# signal1.net
KiCad netlist of a schematic drawn in Altium Designer
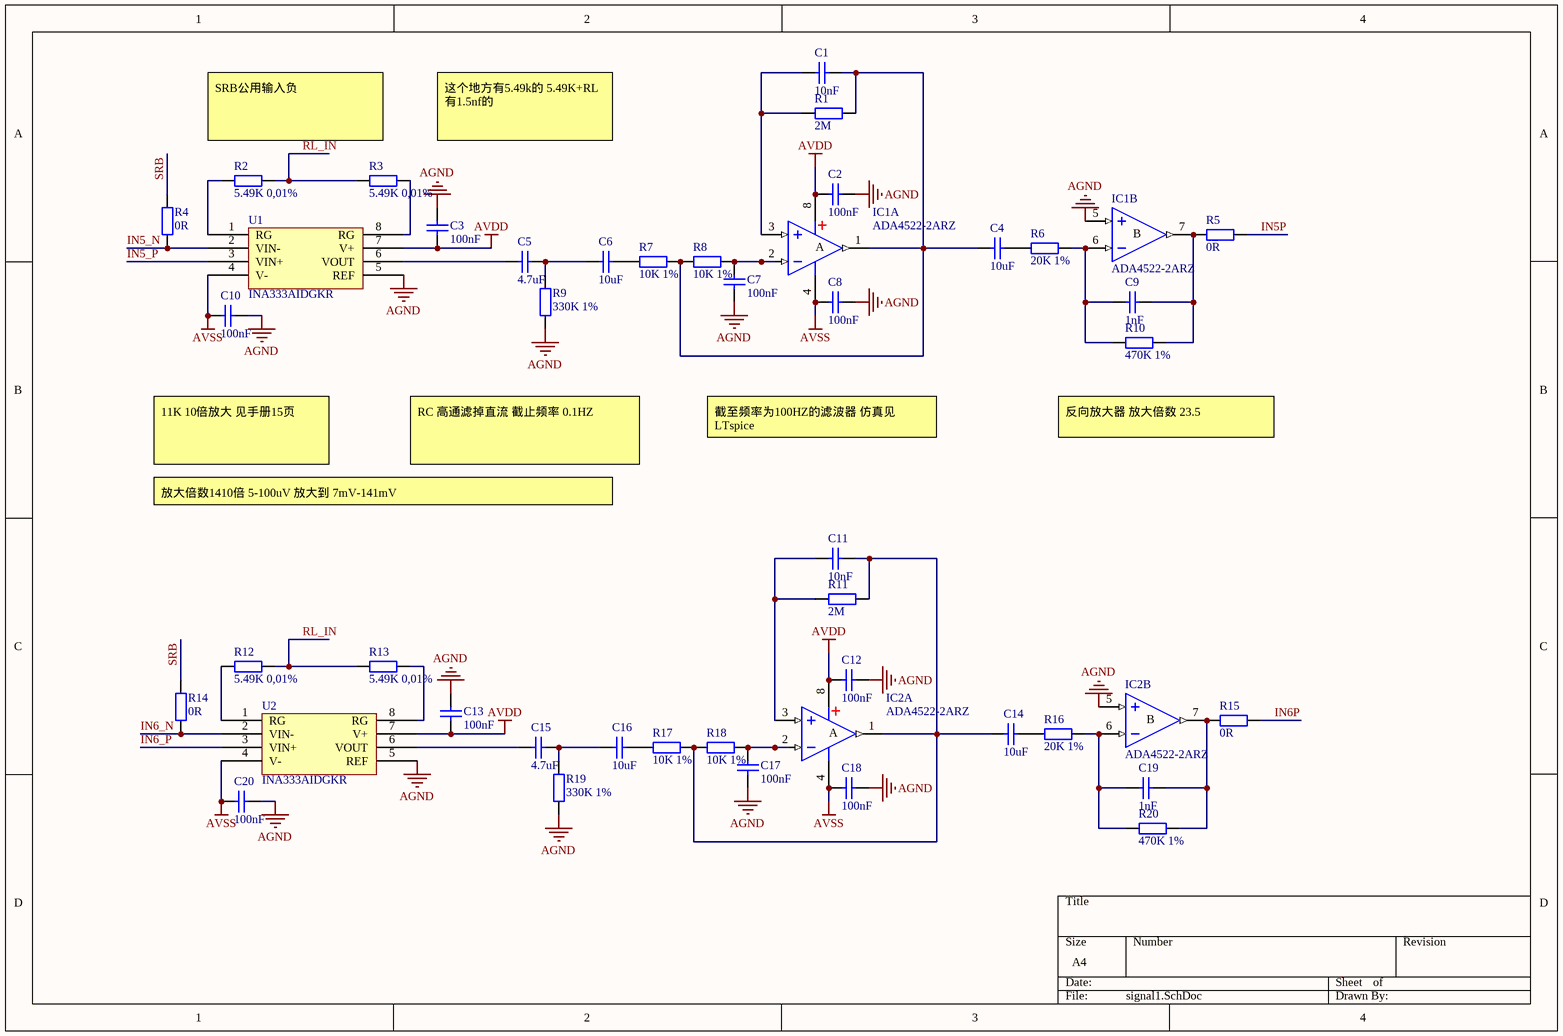
[diagram p0: signal1.SchDoc]

(export (version "E")
  (design (tool "Eeschema 10.0.6"))
  (components
    (comp (ref "C1")
      (value "10nF")
      (footprint "C0603_L")
      (description "贴片电容/MLCC电容")
      (libsource (lib "0.1 - 电阻-电容-电感-保险丝-晶振-晶体-磁珠-电位器-法拉电容-馈通电容") (part "C"))
    )
    (comp (ref "C2")
      (value "100nF")
      (footprint "C0603_L")
      (description "贴片电容/MLCC电容")
      (libsource (lib "0.1 - 电阻-电容-电感-保险丝-晶振-晶体-磁珠-电位器-法拉电容-馈通电容") (part "C"))
    )
    (comp (ref "C3")
      (value "100nF")
      (footprint "C0603_L")
      (description "贴片电容/MLCC电容")
      (libsource (lib "0.1 - 电阻-电容-电感-保险丝-晶振-晶体-磁珠-电位器-法拉电容-馈通电容") (part "C"))
    )
    (comp (ref "C4")
      (value "10uF")
      (footprint "C0603_L")
      (description "贴片电容/MLCC电容")
      (libsource (lib "0.1 - 电阻-电容-电感-保险丝-晶振-晶体-磁珠-电位器-法拉电容-馈通电容") (part "C"))
    )
    (comp (ref "C5")
      (value "4.7uF")
      (footprint "C0603_L")
      (description "贴片电容/MLCC电容")
      (libsource (lib "0.1 - 电阻-电容-电感-保险丝-晶振-晶体-磁珠-电位器-法拉电容-馈通电容") (part "C"))
    )
    (comp (ref "C6")
      (value "10uF")
      (footprint "C0603_L")
      (description "贴片电容/MLCC电容")
      (libsource (lib "0.1 - 电阻-电容-电感-保险丝-晶振-晶体-磁珠-电位器-法拉电容-馈通电容") (part "C"))
    )
    (comp (ref "C7")
      (value "100nF")
      (footprint "C0603_L")
      (description "贴片电容/MLCC电容")
      (libsource (lib "0.1 - 电阻-电容-电感-保险丝-晶振-晶体-磁珠-电位器-法拉电容-馈通电容") (part "C"))
    )
    (comp (ref "C8")
      (value "100nF")
      (footprint "C0603_L")
      (description "贴片电容/MLCC电容")
      (libsource (lib "0.1 - 电阻-电容-电感-保险丝-晶振-晶体-磁珠-电位器-法拉电容-馈通电容") (part "C"))
    )
    (comp (ref "C9")
      (value "1nF")
      (footprint "C0603_L")
      (description "贴片电容/MLCC电容")
      (libsource (lib "0.1 - 电阻-电容-电感-保险丝-晶振-晶体-磁珠-电位器-法拉电容-馈通电容") (part "C"))
    )
    (comp (ref "C10")
      (value "100nF")
      (footprint "C0603_L")
      (description "贴片电容/MLCC电容")
      (libsource (lib "0.1 - 电阻-电容-电感-保险丝-晶振-晶体-磁珠-电位器-法拉电容-馈通电容") (part "C"))
    )
    (comp (ref "C11")
      (value "10nF")
      (footprint "C0603_L")
      (description "贴片电容/MLCC电容")
      (libsource (lib "0.1 - 电阻-电容-电感-保险丝-晶振-晶体-磁珠-电位器-法拉电容-馈通电容") (part "C"))
    )
    (comp (ref "C12")
      (value "100nF")
      (footprint "C0603_L")
      (description "贴片电容/MLCC电容")
      (libsource (lib "0.1 - 电阻-电容-电感-保险丝-晶振-晶体-磁珠-电位器-法拉电容-馈通电容") (part "C"))
    )
    (comp (ref "C13")
      (value "100nF")
      (footprint "C0603_L")
      (description "贴片电容/MLCC电容")
      (libsource (lib "0.1 - 电阻-电容-电感-保险丝-晶振-晶体-磁珠-电位器-法拉电容-馈通电容") (part "C"))
    )
    (comp (ref "C14")
      (value "10uF")
      (footprint "C0603_L")
      (description "贴片电容/MLCC电容")
      (libsource (lib "0.1 - 电阻-电容-电感-保险丝-晶振-晶体-磁珠-电位器-法拉电容-馈通电容") (part "C"))
    )
    (comp (ref "C15")
      (value "4.7uF")
      (footprint "C0603_L")
      (description "贴片电容/MLCC电容")
      (libsource (lib "0.1 - 电阻-电容-电感-保险丝-晶振-晶体-磁珠-电位器-法拉电容-馈通电容") (part "C"))
    )
    (comp (ref "C16")
      (value "10uF")
      (footprint "C0603_L")
      (description "贴片电容/MLCC电容")
      (libsource (lib "0.1 - 电阻-电容-电感-保险丝-晶振-晶体-磁珠-电位器-法拉电容-馈通电容") (part "C"))
    )
    (comp (ref "C17")
      (value "100nF")
      (footprint "C0603_L")
      (description "贴片电容/MLCC电容")
      (libsource (lib "0.1 - 电阻-电容-电感-保险丝-晶振-晶体-磁珠-电位器-法拉电容-馈通电容") (part "C"))
    )
    (comp (ref "C18")
      (value "100nF")
      (footprint "C0603_L")
      (description "贴片电容/MLCC电容")
      (libsource (lib "0.1 - 电阻-电容-电感-保险丝-晶振-晶体-磁珠-电位器-法拉电容-馈通电容") (part "C"))
    )
    (comp (ref "C19")
      (value "1nF")
      (footprint "C0603_L")
      (description "贴片电容/MLCC电容")
      (libsource (lib "0.1 - 电阻-电容-电感-保险丝-晶振-晶体-磁珠-电位器-法拉电容-馈通电容") (part "C"))
    )
    (comp (ref "C20")
      (value "100nF")
      (footprint "C0603_L")
      (description "贴片电容/MLCC电容")
      (libsource (lib "0.1 - 电阻-电容-电感-保险丝-晶振-晶体-磁珠-电位器-法拉电容-馈通电容") (part "C"))
    )
    (comp (ref "IC1")
      (value "ADA4522-2ARZ")
      (footprint "SOIC-8")
      (description "双通道55V、EMI增强型、零漂移、超低噪声、RRO运算放大器")
      (libsource (lib "HT") (part "ADA4522-2ARZ"))
    )
    (comp (ref "IC2")
      (value "ADA4522-2ARZ")
      (footprint "SOIC-8")
      (description "双通道55V、EMI增强型、零漂移、超低噪声、RRO运算放大器")
      (libsource (lib "HT") (part "ADA4522-2ARZ"))
    )
    (comp (ref "R1")
      (value "2M")
      (footprint "R0603_L")
      (description "贴片电阻")
      (libsource (lib "0.1 - 电阻-电容-电感-保险丝-晶振-晶体-磁珠-电位器-法拉电容-馈通电容") (part "R"))
    )
    (comp (ref "R2")
      (value "5.49K 0,01%")
      (footprint "R0603_M")
      (description "贴片电阻")
      (libsource (lib "0.1 - 电阻-电容-电感-保险丝-晶振-晶体-磁珠-电位器-法拉电容-馈通电容") (part "R"))
    )
    (comp (ref "R3")
      (value "5.49K 0,01%")
      (footprint "R0603_M")
      (description "贴片电阻")
      (libsource (lib "0.1 - 电阻-电容-电感-保险丝-晶振-晶体-磁珠-电位器-法拉电容-馈通电容") (part "R"))
    )
    (comp (ref "R4")
      (value "0R")
      (footprint "R0603_L")
      (description "贴片电阻")
      (libsource (lib "0.1 - 电阻-电容-电感-保险丝-晶振-晶体-磁珠-电位器-法拉电容-馈通电容") (part "R"))
    )
    (comp (ref "R5")
      (value "0R")
      (footprint "R0603_L")
      (description "贴片电阻")
      (libsource (lib "0.1 - 电阻-电容-电感-保险丝-晶振-晶体-磁珠-电位器-法拉电容-馈通电容") (part "R"))
    )
    (comp (ref "R6")
      (value "20K 1%")
      (footprint "R0603_L")
      (description "贴片电阻")
      (libsource (lib "0.1 - 电阻-电容-电感-保险丝-晶振-晶体-磁珠-电位器-法拉电容-馈通电容") (part "R"))
    )
    (comp (ref "R7")
      (value "10K 1%")
      (footprint "R0603_L")
      (description "贴片电阻")
      (libsource (lib "0.1 - 电阻-电容-电感-保险丝-晶振-晶体-磁珠-电位器-法拉电容-馈通电容") (part "R"))
    )
    (comp (ref "R8")
      (value "10K 1%")
      (footprint "R0603_L")
      (description "贴片电阻")
      (libsource (lib "0.1 - 电阻-电容-电感-保险丝-晶振-晶体-磁珠-电位器-法拉电容-馈通电容") (part "R"))
    )
    (comp (ref "R9")
      (value "330K 1%")
      (footprint "R0603_L")
      (description "贴片电阻")
      (libsource (lib "0.1 - 电阻-电容-电感-保险丝-晶振-晶体-磁珠-电位器-法拉电容-馈通电容") (part "R"))
    )
    (comp (ref "R10")
      (value "470K 1%")
      (footprint "R0603_L")
      (description "贴片电阻")
      (libsource (lib "0.1 - 电阻-电容-电感-保险丝-晶振-晶体-磁珠-电位器-法拉电容-馈通电容") (part "R"))
    )
    (comp (ref "R11")
      (value "2M")
      (footprint "R0603_L")
      (description "贴片电阻")
      (libsource (lib "0.1 - 电阻-电容-电感-保险丝-晶振-晶体-磁珠-电位器-法拉电容-馈通电容") (part "R"))
    )
    (comp (ref "R12")
      (value "5.49K 0,01%")
      (footprint "R0603_M")
      (description "贴片电阻")
      (libsource (lib "0.1 - 电阻-电容-电感-保险丝-晶振-晶体-磁珠-电位器-法拉电容-馈通电容") (part "R"))
    )
    (comp (ref "R13")
      (value "5.49K 0,01%")
      (footprint "R0603_M")
      (description "贴片电阻")
      (libsource (lib "0.1 - 电阻-电容-电感-保险丝-晶振-晶体-磁珠-电位器-法拉电容-馈通电容") (part "R"))
    )
    (comp (ref "R14")
      (value "0R")
      (footprint "R0603_L")
      (description "贴片电阻")
      (libsource (lib "0.1 - 电阻-电容-电感-保险丝-晶振-晶体-磁珠-电位器-法拉电容-馈通电容") (part "R"))
    )
    (comp (ref "R15")
      (value "0R")
      (footprint "R0603_L")
      (description "贴片电阻")
      (libsource (lib "0.1 - 电阻-电容-电感-保险丝-晶振-晶体-磁珠-电位器-法拉电容-馈通电容") (part "R"))
    )
    (comp (ref "R16")
      (value "20K 1%")
      (footprint "R0603_L")
      (description "贴片电阻")
      (libsource (lib "0.1 - 电阻-电容-电感-保险丝-晶振-晶体-磁珠-电位器-法拉电容-馈通电容") (part "R"))
    )
    (comp (ref "R17")
      (value "10K 1%")
      (footprint "R0603_L")
      (description "贴片电阻")
      (libsource (lib "0.1 - 电阻-电容-电感-保险丝-晶振-晶体-磁珠-电位器-法拉电容-馈通电容") (part "R"))
    )
    (comp (ref "R18")
      (value "10K 1%")
      (footprint "R0603_L")
      (description "贴片电阻")
      (libsource (lib "0.1 - 电阻-电容-电感-保险丝-晶振-晶体-磁珠-电位器-法拉电容-馈通电容") (part "R"))
    )
    (comp (ref "R19")
      (value "330K 1%")
      (footprint "R0603_L")
      (description "贴片电阻")
      (libsource (lib "0.1 - 电阻-电容-电感-保险丝-晶振-晶体-磁珠-电位器-法拉电容-馈通电容") (part "R"))
    )
    (comp (ref "R20")
      (value "470K 1%")
      (footprint "R0603_L")
      (description "贴片电阻")
      (libsource (lib "0.1 - 电阻-电容-电感-保险丝-晶振-晶体-磁珠-电位器-法拉电容-馈通电容") (part "R"))
    )
    (comp (ref "U1")
      (value "INA333AIDGKR")
      (footprint "MSOP8_N")
      (description "INA333 低功耗、零漂移、精密仪表放大器")
      (libsource (lib "HT") (part "INA333AIDGKR"))
    )
    (comp (ref "U2")
      (value "INA333AIDGKR")
      (footprint "MSOP8_N")
      (description "INA333 低功耗、零漂移、精密仪表放大器")
      (libsource (lib "HT") (part "INA333AIDGKR"))
    )
  )
  (nets
    (net (code "1") (name "/IN5P") (class "Default")
      (node (ref "R5") (pin "1") (pinfunction "1_1") (pintype "passive"))
    )
    (net (code "2") (name "/IN5_N") (class "Default")
      (node (ref "R4") (pin "2") (pinfunction "2_2") (pintype "passive"))
      (node (ref "U1") (pin "2") (pinfunction "VIN-_2") (pintype "passive"))
    )
    (net (code "3") (name "/IN5_P") (class "Default")
      (node (ref "U1") (pin "3") (pinfunction "VIN+_3") (pintype "passive"))
    )
    (net (code "4") (name "/IN6P") (class "Default")
      (node (ref "R15") (pin "1") (pinfunction "1_1") (pintype "passive"))
    )
    (net (code "5") (name "/IN6_N") (class "Default")
      (node (ref "R14") (pin "2") (pinfunction "2_2") (pintype "passive"))
      (node (ref "U2") (pin "2") (pinfunction "VIN-_2") (pintype "passive"))
    )
    (net (code "6") (name "/IN6_P") (class "Default")
      (node (ref "U2") (pin "3") (pinfunction "VIN+_3") (pintype "passive"))
    )
    (net (code "7") (name "/RL_IN") (class "Default")
      (node (ref "R12") (pin "2") (pinfunction "2_2") (pintype "passive"))
      (node (ref "R13") (pin "1") (pinfunction "1_1") (pintype "passive"))
      (node (ref "R2") (pin "2") (pinfunction "2_2") (pintype "passive"))
      (node (ref "R3") (pin "1") (pinfunction "1_1") (pintype "passive"))
    )
    (net (code "8") (name "/SRB") (class "Default")
      (node (ref "R14") (pin "1") (pinfunction "1_1") (pintype "passive"))
      (node (ref "R4") (pin "1") (pinfunction "1_1") (pintype "passive"))
    )
    (net (code "9") (name "AGND") (class "Default")
      (node (ref "C10") (pin "1") (pinfunction "1_1") (pintype "passive"))
      (node (ref "C12") (pin "2") (pinfunction "2_2") (pintype "passive"))
      (node (ref "C13") (pin "1") (pinfunction "1_1") (pintype "passive"))
      (node (ref "C17") (pin "1") (pinfunction "1_1") (pintype "passive"))
      (node (ref "C18") (pin "2") (pinfunction "2_2") (pintype "passive"))
      (node (ref "C2") (pin "2") (pinfunction "2_2") (pintype "passive"))
      (node (ref "C20") (pin "1") (pinfunction "1_1") (pintype "passive"))
      (node (ref "C3") (pin "1") (pinfunction "1_1") (pintype "passive"))
      (node (ref "C7") (pin "1") (pinfunction "1_1") (pintype "passive"))
      (node (ref "C8") (pin "2") (pinfunction "2_2") (pintype "passive"))
      (node (ref "IC1") (pin "5") (pinfunction "IN+_5") (pintype "input"))
      (node (ref "IC2") (pin "5") (pinfunction "IN+_5") (pintype "input"))
      (node (ref "R19") (pin "1") (pinfunction "1_1") (pintype "passive"))
      (node (ref "R9") (pin "1") (pinfunction "1_1") (pintype "passive"))
      (node (ref "U1") (pin "5") (pinfunction "REF_5") (pintype "passive"))
      (node (ref "U2") (pin "5") (pinfunction "REF_5") (pintype "passive"))
    )
    (net (code "10") (name "AVDD") (class "Default")
      (node (ref "C12") (pin "1") (pinfunction "1_1") (pintype "passive"))
      (node (ref "C13") (pin "2") (pinfunction "2_2") (pintype "passive"))
      (node (ref "C2") (pin "1") (pinfunction "1_1") (pintype "passive"))
      (node (ref "C3") (pin "2") (pinfunction "2_2") (pintype "passive"))
      (node (ref "IC1") (pin "8") (pinfunction "V+_8") (pintype "power_in"))
      (node (ref "IC2") (pin "8") (pinfunction "V+_8") (pintype "power_in"))
      (node (ref "U1") (pin "7") (pinfunction "V+_7") (pintype "passive"))
      (node (ref "U2") (pin "7") (pinfunction "V+_7") (pintype "passive"))
    )
    (net (code "11") (name "AVSS") (class "Default")
      (node (ref "C10") (pin "2") (pinfunction "2_2") (pintype "passive"))
      (node (ref "C18") (pin "1") (pinfunction "1_1") (pintype "passive"))
      (node (ref "C20") (pin "2") (pinfunction "2_2") (pintype "passive"))
      (node (ref "C8") (pin "1") (pinfunction "1_1") (pintype "passive"))
      (node (ref "IC1") (pin "4") (pinfunction "V-_4") (pintype "power_in"))
      (node (ref "IC2") (pin "4") (pinfunction "V-_4") (pintype "power_in"))
      (node (ref "U1") (pin "4") (pinfunction "V-_4") (pintype "passive"))
      (node (ref "U2") (pin "4") (pinfunction "V-_4") (pintype "passive"))
    )
    (net (code "12") (name "Net-(C4-Pad2)") (class "Default")
      (node (ref "C4") (pin "2") (pinfunction "2_2") (pintype "passive"))
      (node (ref "R6") (pin "2") (pinfunction "2_2") (pintype "passive"))
    )
    (net (code "13") (name "Net-(C5-Pad2)") (class "Default")
      (node (ref "C5") (pin "2") (pinfunction "2_2") (pintype "passive"))
      (node (ref "C6") (pin "1") (pinfunction "1_1") (pintype "passive"))
      (node (ref "R9") (pin "2") (pinfunction "2_2") (pintype "passive"))
    )
    (net (code "14") (name "Net-(C6-Pad2)") (class "Default")
      (node (ref "C6") (pin "2") (pinfunction "2_2") (pintype "passive"))
      (node (ref "R7") (pin "2") (pinfunction "2_2") (pintype "passive"))
    )
    (net (code "15") (name "Net-(C14-Pad2)") (class "Default")
      (node (ref "C14") (pin "2") (pinfunction "2_2") (pintype "passive"))
      (node (ref "R16") (pin "2") (pinfunction "2_2") (pintype "passive"))
    )
    (net (code "16") (name "Net-(C15-Pad2)") (class "Default")
      (node (ref "C15") (pin "2") (pinfunction "2_2") (pintype "passive"))
      (node (ref "C16") (pin "1") (pinfunction "1_1") (pintype "passive"))
      (node (ref "R19") (pin "2") (pinfunction "2_2") (pintype "passive"))
    )
    (net (code "17") (name "Net-(C16-Pad2)") (class "Default")
      (node (ref "C16") (pin "2") (pinfunction "2_2") (pintype "passive"))
      (node (ref "R17") (pin "2") (pinfunction "2_2") (pintype "passive"))
    )
    (net (code "18") (name "Net-(IC1A-IN+)") (class "Default")
      (node (ref "C1") (pin "1") (pinfunction "1_1") (pintype "passive"))
      (node (ref "IC1") (pin "3") (pinfunction "IN+_3") (pintype "input"))
      (node (ref "R1") (pin "2") (pinfunction "2_2") (pintype "passive"))
    )
    (net (code "19") (name "Net-(IC1A-IN-)") (class "Default")
      (node (ref "C7") (pin "2") (pinfunction "2_2") (pintype "passive"))
      (node (ref "IC1") (pin "2") (pinfunction "IN-_2") (pintype "input"))
      (node (ref "R8") (pin "1") (pinfunction "1_1") (pintype "passive"))
    )
    (net (code "20") (name "Net-(IC1A-OUT)") (class "Default")
      (node (ref "C1") (pin "2") (pinfunction "2_2") (pintype "passive"))
      (node (ref "C4") (pin "1") (pinfunction "1_1") (pintype "passive"))
      (node (ref "IC1") (pin "1") (pinfunction "OUT_1") (pintype "output"))
      (node (ref "R1") (pin "1") (pinfunction "1_1") (pintype "passive"))
      (node (ref "R7") (pin "1") (pinfunction "1_1") (pintype "passive"))
      (node (ref "R8") (pin "2") (pinfunction "2_2") (pintype "passive"))
    )
    (net (code "21") (name "Net-(IC1B-IN-)") (class "Default")
      (node (ref "C9") (pin "1") (pinfunction "1_1") (pintype "passive"))
      (node (ref "IC1") (pin "6") (pinfunction "IN-_6") (pintype "input"))
      (node (ref "R10") (pin "2") (pinfunction "2_2") (pintype "passive"))
      (node (ref "R6") (pin "1") (pinfunction "1_1") (pintype "passive"))
    )
    (net (code "22") (name "Net-(IC1B-OUT)") (class "Default")
      (node (ref "C9") (pin "2") (pinfunction "2_2") (pintype "passive"))
      (node (ref "IC1") (pin "7") (pinfunction "OUT_7") (pintype "output"))
      (node (ref "R10") (pin "1") (pinfunction "1_1") (pintype "passive"))
      (node (ref "R5") (pin "2") (pinfunction "2_2") (pintype "passive"))
    )
    (net (code "23") (name "Net-(IC2A-IN+)") (class "Default")
      (node (ref "C11") (pin "1") (pinfunction "1_1") (pintype "passive"))
      (node (ref "IC2") (pin "3") (pinfunction "IN+_3") (pintype "input"))
      (node (ref "R11") (pin "2") (pinfunction "2_2") (pintype "passive"))
    )
    (net (code "24") (name "Net-(IC2A-IN-)") (class "Default")
      (node (ref "C17") (pin "2") (pinfunction "2_2") (pintype "passive"))
      (node (ref "IC2") (pin "2") (pinfunction "IN-_2") (pintype "input"))
      (node (ref "R18") (pin "1") (pinfunction "1_1") (pintype "passive"))
    )
    (net (code "25") (name "Net-(IC2A-OUT)") (class "Default")
      (node (ref "C11") (pin "2") (pinfunction "2_2") (pintype "passive"))
      (node (ref "C14") (pin "1") (pinfunction "1_1") (pintype "passive"))
      (node (ref "IC2") (pin "1") (pinfunction "OUT_1") (pintype "output"))
      (node (ref "R11") (pin "1") (pinfunction "1_1") (pintype "passive"))
      (node (ref "R17") (pin "1") (pinfunction "1_1") (pintype "passive"))
      (node (ref "R18") (pin "2") (pinfunction "2_2") (pintype "passive"))
    )
    (net (code "26") (name "Net-(IC2B-IN-)") (class "Default")
      (node (ref "C19") (pin "1") (pinfunction "1_1") (pintype "passive"))
      (node (ref "IC2") (pin "6") (pinfunction "IN-_6") (pintype "input"))
      (node (ref "R16") (pin "1") (pinfunction "1_1") (pintype "passive"))
      (node (ref "R20") (pin "2") (pinfunction "2_2") (pintype "passive"))
    )
    (net (code "27") (name "Net-(IC2B-OUT)") (class "Default")
      (node (ref "C19") (pin "2") (pinfunction "2_2") (pintype "passive"))
      (node (ref "IC2") (pin "7") (pinfunction "OUT_7") (pintype "output"))
      (node (ref "R15") (pin "2") (pinfunction "2_2") (pintype "passive"))
      (node (ref "R20") (pin "1") (pinfunction "1_1") (pintype "passive"))
    )
    (net (code "28") (name "Net-(R2-Pad1)") (class "Default")
      (node (ref "R2") (pin "1") (pinfunction "1_1") (pintype "passive"))
      (node (ref "U1") (pin "1") (pinfunction "RG_1") (pintype "passive"))
    )
    (net (code "29") (name "Net-(R3-Pad2)") (class "Default")
      (node (ref "R3") (pin "2") (pinfunction "2_2") (pintype "passive"))
      (node (ref "U1") (pin "8") (pinfunction "RG_8") (pintype "passive"))
    )
    (net (code "30") (name "Net-(R12-Pad1)") (class "Default")
      (node (ref "R12") (pin "1") (pinfunction "1_1") (pintype "passive"))
      (node (ref "U2") (pin "1") (pinfunction "RG_1") (pintype "passive"))
    )
    (net (code "31") (name "Net-(R13-Pad2)") (class "Default")
      (node (ref "R13") (pin "2") (pinfunction "2_2") (pintype "passive"))
      (node (ref "U2") (pin "8") (pinfunction "RG_8") (pintype "passive"))
    )
    (net (code "32") (name "Net-(U1-VOUT)") (class "Default")
      (node (ref "C5") (pin "1") (pinfunction "1_1") (pintype "passive"))
      (node (ref "U1") (pin "6") (pinfunction "VOUT_6") (pintype "passive"))
    )
    (net (code "33") (name "Net-(U2-VOUT)") (class "Default")
      (node (ref "C15") (pin "1") (pinfunction "1_1") (pintype "passive"))
      (node (ref "U2") (pin "6") (pinfunction "VOUT_6") (pintype "passive"))
    )
  )
)
